# Controller.net
KiCad netlist of a schematic drawn in Altium Designer
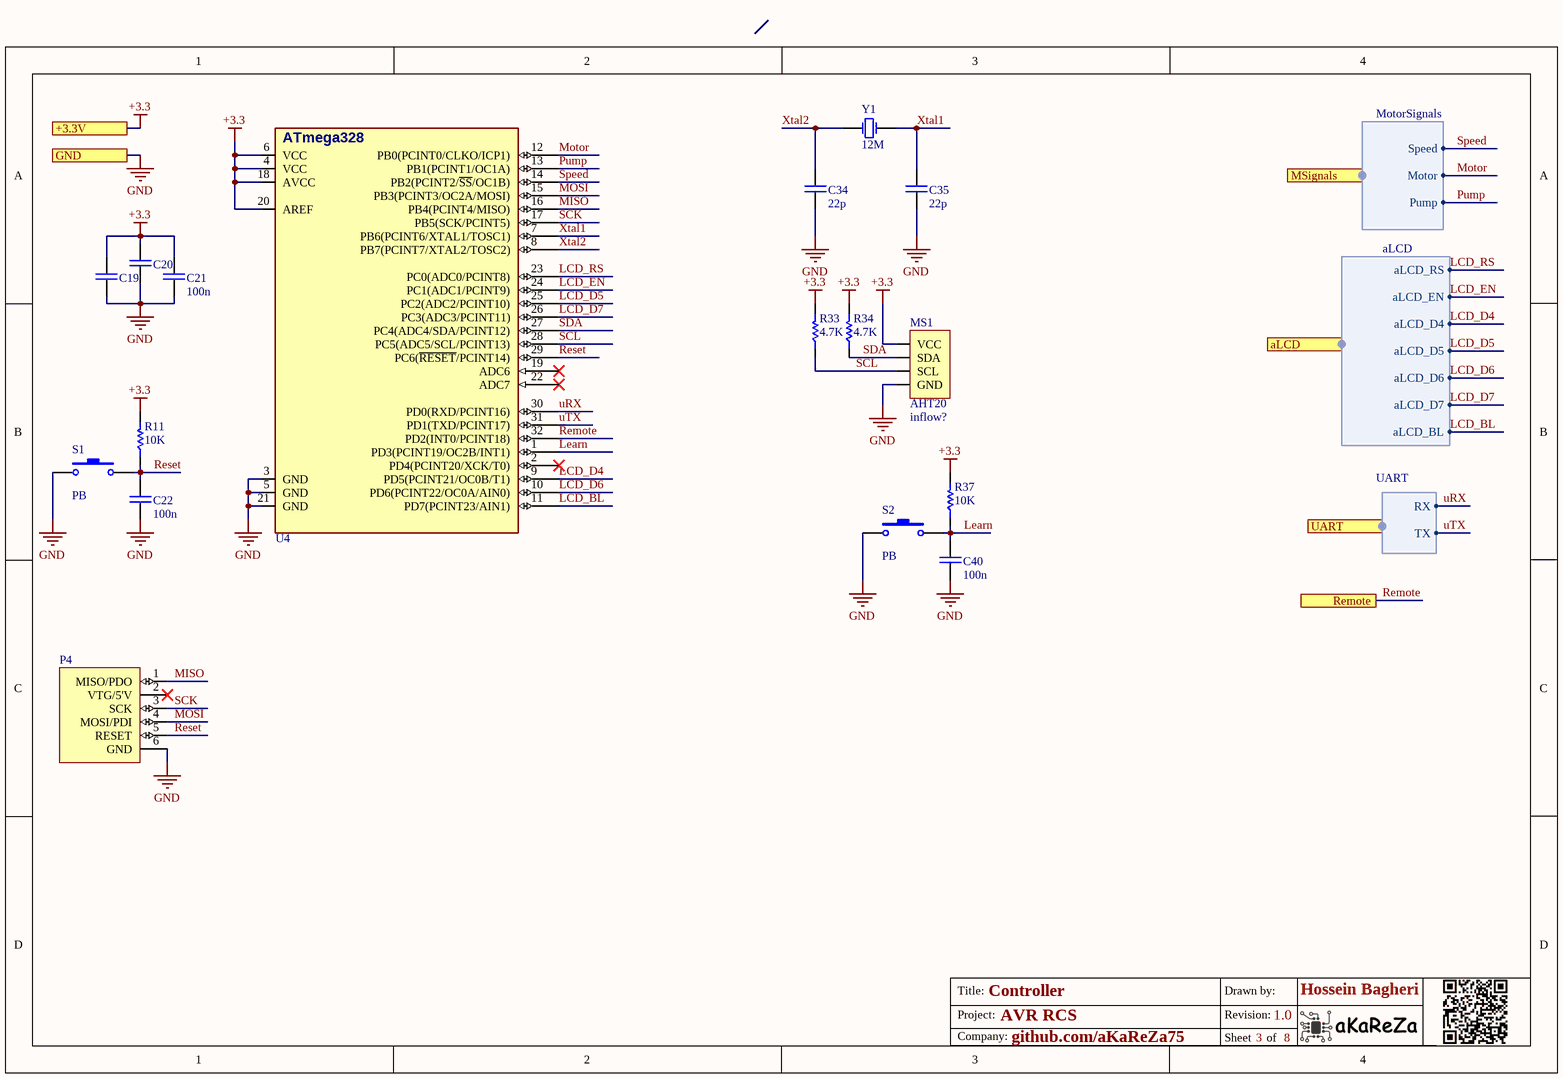
[diagram p0: Controller.SchDoc]

(export (version "E")
  (design (tool "Eeschema 10.0.6"))
  (components
    (comp (ref "C19")
      (value "100n")
      (footprint "CAP 0805/2012")
      (description "Bipolar ceramic capacitor SMD")
      (fields (field (name "VALIDATION") "Valid"))
      (libsource (lib "aKaReZa") (part "Cap_Multi_SMD_100nF_0805"))
    )
    (comp (ref "C20")
      (value "100n")
      (footprint "CAP 0805/2012")
      (description "Bipolar ceramic capacitor SMD")
      (fields (field (name "VALIDATION") "Valid"))
      (libsource (lib "aKaReZa") (part "Cap_Multi_SMD_100nF_0805"))
    )
    (comp (ref "C21")
      (value "100n")
      (footprint "CAP 0805/2012")
      (description "Bipolar ceramic capacitor SMD")
      (fields (field (name "VALIDATION") "Valid"))
      (libsource (lib "aKaReZa") (part "Cap_Multi_SMD_100nF_0805"))
    )
    (comp (ref "C22")
      (value "100n")
      (footprint "CAP 0805/2012")
      (description "Bipolar ceramic capacitor SMD")
      (fields (field (name "VALIDATION") "Valid"))
      (libsource (lib "aKaReZa") (part "Cap_Multi_SMD_100nF_0805"))
    )
    (comp (ref "C34")
      (value "22p")
      (footprint "CAP 0805/2012")
      (description "Bipolar ceramic capacitor SMD")
      (fields (field (name "VALIDATION") "Valid"))
      (libsource (lib "aKaReZa") (part "Cap_Multi_SMD_0805"))
    )
    (comp (ref "C35")
      (value "22p")
      (footprint "CAP 0805/2012")
      (description "Bipolar ceramic capacitor SMD")
      (fields (field (name "VALIDATION") "Valid"))
      (libsource (lib "aKaReZa") (part "Cap_Multi_SMD_0805"))
    )
    (comp (ref "C40")
      (value "100n")
      (footprint "CAP 0805/2012")
      (description "Bipolar ceramic capacitor SMD")
      (fields (field (name "VALIDATION") "Valid"))
      (libsource (lib "aKaReZa") (part "Cap_Multi_SMD_100nF_0805"))
    )
    (comp (ref "MS1")
      (value "AHT20")
      (footprint "AHT20")
      (description "Air Temperature and Humidity Sensor")
      (fields (field (name "INFLOW") "inflow?") (field (name "VALIDATION") "NT"))
      (libsource (lib "aKaReZa") (part "ModSen_AHT20"))
    )
    (comp (ref "P4")
      (value "3x2")
      (footprint "IDC_2X3")
      (description "6 Pin Standard ISP Header For MKII")
      (fields (field (name "VALIDATION") "NT"))
      (libsource (lib "aKaReZa") (part "Con_Prog_MKII_ISP"))
    )
    (comp (ref "R11")
      (value "10K")
      (footprint "RES 0805 (2012X06L)")
      (description "Resistor")
      (fields (field (name "VALIDATION") "Valid"))
      (libsource (lib "aKaReZa") (part "Res_SMD_0805"))
    )
    (comp (ref "R33")
      (value "4.7K")
      (footprint "RES 0805 (2012X06L)")
      (description "Resistor")
      (fields (field (name "VALIDATION") "Valid"))
      (libsource (lib "aKaReZa") (part "Res_SMD_0805"))
    )
    (comp (ref "R34")
      (value "4.7K")
      (footprint "RES 0805 (2012X06L)")
      (description "Resistor")
      (fields (field (name "VALIDATION") "Valid"))
      (libsource (lib "aKaReZa") (part "Res_SMD_0805"))
    )
    (comp (ref "R37")
      (value "10K")
      (footprint "RES 0805 (2012X06L)")
      (description "Resistor")
      (fields (field (name "VALIDATION") "Valid"))
      (libsource (lib "aKaReZa") (part "Res_SMD_0805"))
    )
    (comp (ref "S1")
      (value "PB")
      (footprint "SW_PB_SMD_2PIN_SPST_6X3X2")
      (description "SMT Tactile ‎Switch")
      (fields (field (name "VALIDATION") "Valid"))
      (libsource (lib "aKaReZa") (part "SW_PushButton_2_SMD"))
    )
    (comp (ref "S2")
      (value "PB")
      (footprint "SW_PB_SMD_2PIN_SPST_6X3X2")
      (description "SMT Tactile ‎Switch")
      (fields (field (name "VALIDATION") "Valid"))
      (libsource (lib "aKaReZa") (part "SW_PushButton_2_SMD"))
    )
    (comp (ref "U4")
      (value "ATmega328P")
      (footprint "ATMEGA328")
      (description "8-Bit AVR Microcontroller with 32K Bytes of In-System Programmable Flash Memory")
      (fields (field (name "VALIDATION") "Valid"))
      (libsource (lib "aKaReZa") (part "IC_MCU_ATmega328P_SMD"))
    )
    (comp (ref "Y1")
      (value "12M")
      (footprint "Crystal SMD")
      (description "Crystal Oscillator")
      (fields (field (name "VALIDATION") "Valid"))
      (libsource (lib "aKaReZa") (part "Other_Elec_Xtal_SMD"))
    )
  )
  (nets
    (net (code "4") (name "+3.3") (class "Default")
      (node (ref "C19") (pin "1") (pinfunction "1_1") (pintype "passive"))
      (node (ref "C20") (pin "1") (pinfunction "1_1") (pintype "passive"))
      (node (ref "C21") (pin "1") (pinfunction "1_1") (pintype "passive"))
      (node (ref "MS1") (pin "4") (pinfunction "VCC_4") (pintype "passive"))
      (node (ref "R11") (pin "2") (pinfunction "2_2") (pintype "passive"))
      (node (ref "R33") (pin "2") (pinfunction "2_2") (pintype "passive"))
      (node (ref "R34") (pin "2") (pinfunction "2_2") (pintype "passive"))
      (node (ref "R37") (pin "2") (pinfunction "2_2") (pintype "passive"))
      (node (ref "U4") (pin "18") (pinfunction "AVCC_18") (pintype "power_in"))
      (node (ref "U4") (pin "20") (pinfunction "AREF_20") (pintype "passive"))
      (node (ref "U4") (pin "4") (pinfunction "VCC_4") (pintype "power_in"))
      (node (ref "U4") (pin "6") (pinfunction "VCC_6") (pintype "power_in"))
    )
    (net (code "5") (name "/LCD_BL") (class "Default")
      (node (ref "U4") (pin "11") (pinfunction "PD7(PCINT23/AIN1)_11") (pintype "bidirectional"))
    )
    (net (code "6") (name "/LCD_D4") (class "Default")
      (node (ref "U4") (pin "9") (pinfunction "PD5(PCINT21/OC0B/T1)_9") (pintype "bidirectional"))
    )
    (net (code "7") (name "/LCD_D5") (class "Default")
      (node (ref "U4") (pin "25") (pinfunction "PC2(ADC2/PCINT10)_25") (pintype "bidirectional"))
    )
    (net (code "8") (name "/LCD_D6") (class "Default")
      (node (ref "U4") (pin "10") (pinfunction "PD6(PCINT22/OC0A/AIN0)_10") (pintype "bidirectional"))
    )
    (net (code "9") (name "/LCD_D7") (class "Default")
      (node (ref "U4") (pin "26") (pinfunction "PC3(ADC3/PCINT11)_26") (pintype "bidirectional"))
    )
    (net (code "10") (name "/LCD_EN") (class "Default")
      (node (ref "U4") (pin "24") (pinfunction "PC1(ADC1/PCINT9)_24") (pintype "bidirectional"))
    )
    (net (code "11") (name "/LCD_RS") (class "Default")
      (node (ref "U4") (pin "23") (pinfunction "PC0(ADC0/PCINT8)_23") (pintype "bidirectional"))
    )
    (net (code "12") (name "/Learn") (class "Default")
      (node (ref "C40") (pin "1") (pinfunction "1_1") (pintype "passive"))
      (node (ref "R37") (pin "1") (pinfunction "1_1") (pintype "passive"))
      (node (ref "S2") (pin "2") (pinfunction "2_2") (pintype "passive"))
      (node (ref "U4") (pin "1") (pinfunction "PD3(PCINT19/OC2B/INT1)_1") (pintype "bidirectional"))
    )
    (net (code "13") (name "/MISO") (class "Default")
      (node (ref "P4") (pin "1") (pinfunction "MISO/PDO_1") (pintype "bidirectional"))
      (node (ref "U4") (pin "16") (pinfunction "PB4(PCINT4/MISO)_16") (pintype "bidirectional"))
    )
    (net (code "14") (name "/MOSI") (class "Default")
      (node (ref "P4") (pin "4") (pinfunction "MOSI/PDI_4") (pintype "bidirectional"))
      (node (ref "U4") (pin "15") (pinfunction "PB3(PCINT3/OC2A/MOSI)_15") (pintype "bidirectional"))
    )
    (net (code "15") (name "/Motor") (class "Default")
      (node (ref "U4") (pin "12") (pinfunction "PB0(PCINT0/CLKO/ICP1)_12") (pintype "bidirectional"))
    )
    (net (code "16") (name "/Pump") (class "Default")
      (node (ref "U4") (pin "13") (pinfunction "PB1(PCINT1/OC1A)_13") (pintype "bidirectional"))
    )
    (net (code "17") (name "/Remote") (class "Default")
      (node (ref "U4") (pin "32") (pinfunction "PD2(INT0/PCINT18)_32") (pintype "bidirectional"))
    )
    (net (code "18") (name "/Reset") (class "Default")
      (node (ref "C22") (pin "1") (pinfunction "1_1") (pintype "passive"))
      (node (ref "P4") (pin "5") (pinfunction "RESET_5") (pintype "bidirectional"))
      (node (ref "R11") (pin "1") (pinfunction "1_1") (pintype "passive"))
      (node (ref "S1") (pin "2") (pinfunction "2_2") (pintype "passive"))
      (node (ref "U4") (pin "29") (pinfunction "PC6(~{RESET}/PCINT14)_29") (pintype "bidirectional"))
    )
    (net (code "19") (name "/SCK") (class "Default")
      (node (ref "P4") (pin "3") (pinfunction "SCK_3") (pintype "bidirectional"))
      (node (ref "U4") (pin "17") (pinfunction "PB5(SCK/PCINT5)_17") (pintype "bidirectional"))
    )
    (net (code "20") (name "/SCL") (class "Default")
      (node (ref "MS1") (pin "2") (pinfunction "SCL_2") (pintype "passive"))
      (node (ref "R33") (pin "1") (pinfunction "1_1") (pintype "passive"))
      (node (ref "U4") (pin "28") (pinfunction "PC5(ADC5/SCL/PCINT13)_28") (pintype "bidirectional"))
    )
    (net (code "21") (name "/SDA") (class "Default")
      (node (ref "MS1") (pin "1") (pinfunction "SDA_1") (pintype "passive"))
      (node (ref "R34") (pin "1") (pinfunction "1_1") (pintype "passive"))
      (node (ref "U4") (pin "27") (pinfunction "PC4(ADC4/SDA/PCINT12)_27") (pintype "bidirectional"))
    )
    (net (code "22") (name "/Speed") (class "Default")
      (node (ref "U4") (pin "14") (pinfunction "PB2(PCINT2/~{SS}/OC1B)_14") (pintype "bidirectional"))
    )
    (net (code "23") (name "/Xtal1") (class "Default")
      (node (ref "C35") (pin "1") (pinfunction "1_1") (pintype "passive"))
      (node (ref "U4") (pin "7") (pinfunction "PB6(PCINT6/XTAL1/TOSC1)_7") (pintype "bidirectional"))
      (node (ref "Y1") (pin "2") (pinfunction "OSC2_2") (pintype "passive"))
    )
    (net (code "24") (name "/Xtal2") (class "Default")
      (node (ref "C34") (pin "1") (pinfunction "1_1") (pintype "passive"))
      (node (ref "U4") (pin "8") (pinfunction "PB7(PCINT7/XTAL2/TOSC2)_8") (pintype "bidirectional"))
      (node (ref "Y1") (pin "1") (pinfunction "OSC1_1") (pintype "passive"))
    )
    (net (code "25") (name "/uRX") (class "Default")
      (node (ref "U4") (pin "30") (pinfunction "PD0(RXD/PCINT16)_30") (pintype "bidirectional"))
    )
    (net (code "26") (name "/uTX") (class "Default")
      (node (ref "U4") (pin "31") (pinfunction "PD1(TXD/PCINT17)_31") (pintype "bidirectional"))
    )
    (net (code "30") (name "GND") (class "Default")
      (node (ref "C19") (pin "2") (pinfunction "2_2") (pintype "passive"))
      (node (ref "C20") (pin "2") (pinfunction "2_2") (pintype "passive"))
      (node (ref "C21") (pin "2") (pinfunction "2_2") (pintype "passive"))
      (node (ref "C22") (pin "2") (pinfunction "2_2") (pintype "passive"))
      (node (ref "C34") (pin "2") (pinfunction "2_2") (pintype "passive"))
      (node (ref "C35") (pin "2") (pinfunction "2_2") (pintype "passive"))
      (node (ref "C40") (pin "2") (pinfunction "2_2") (pintype "passive"))
      (node (ref "MS1") (pin "3") (pinfunction "GND_3") (pintype "passive"))
      (node (ref "P4") (pin "6") (pinfunction "GND_6") (pintype "passive"))
      (node (ref "S1") (pin "1") (pinfunction "1_1") (pintype "passive"))
      (node (ref "S2") (pin "1") (pinfunction "1_1") (pintype "passive"))
      (node (ref "U4") (pin "21") (pinfunction "GND_21") (pintype "power_in"))
      (node (ref "U4") (pin "3") (pinfunction "GND_3") (pintype "power_in"))
      (node (ref "U4") (pin "5") (pinfunction "GND_5") (pintype "power_in"))
    )
    (net (code "31") (name "unconnected-(P4-VTG{slash}5'V-Pad2)") (class "Default")
      (node (ref "P4") (pin "2") (pinfunction "VTG/5'V_2") (pintype "passive+no_connect"))
    )
    (net (code "32") (name "unconnected-(U4-ADC6-Pad19)") (class "Default")
      (node (ref "U4") (pin "19") (pinfunction "ADC6_19") (pintype "input+no_connect"))
    )
    (net (code "33") (name "unconnected-(U4-ADC7-Pad22)") (class "Default")
      (node (ref "U4") (pin "22") (pinfunction "ADC7_22") (pintype "input+no_connect"))
    )
    (net (code "34") (name "unconnected-(U4-PD4(PCINT20{slash}XCK{slash}T0)-Pad2)") (class "Default")
      (node (ref "U4") (pin "2") (pinfunction "PD4(PCINT20/XCK/T0)_2") (pintype "bidirectional+no_connect"))
    )
  )
)
